# top.net
KiCad netlist of a schematic drawn in Altium Designer
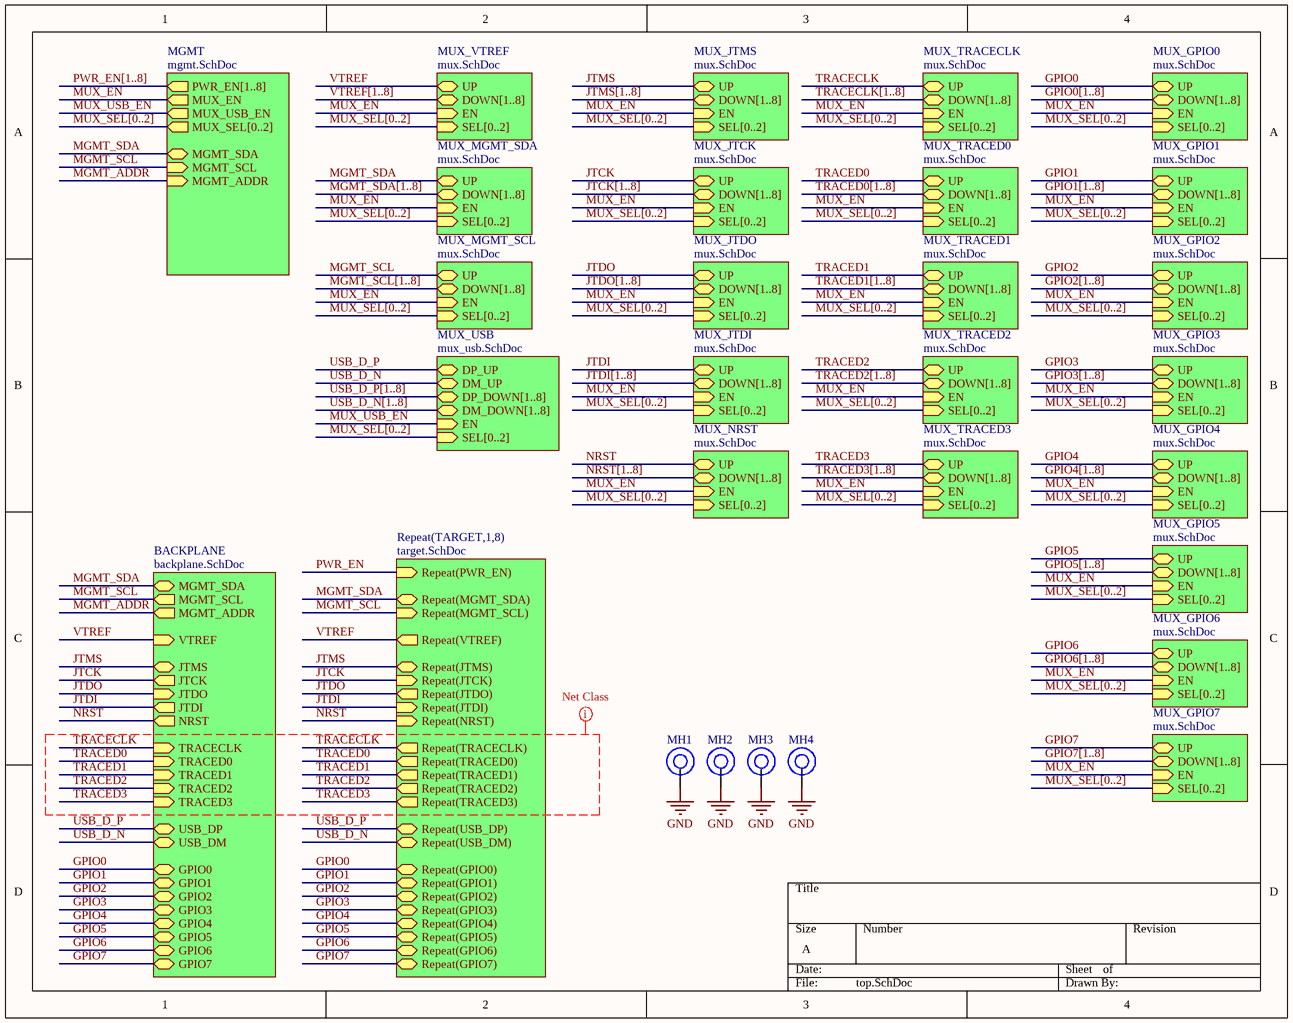
[diagram p0: top.SchDoc]

(export (version "E")
  (design (tool "Eeschema 10.0.6"))
  (components
    (comp (ref "MH1")
      (value "Mounting_Hole")
      (footprint "WA-SMSI_M2.5")
      (libsource (lib "misc") (part "Mounting_Hole"))
    )
    (comp (ref "MH2")
      (value "Mounting_Hole")
      (footprint "WA-SMSI_M2.5")
      (libsource (lib "misc") (part "Mounting_Hole"))
    )
    (comp (ref "MH3")
      (value "Mounting_Hole")
      (footprint "WA-SMSI_M2.5")
      (libsource (lib "misc") (part "Mounting_Hole"))
    )
    (comp (ref "MH4")
      (value "Mounting_Hole")
      (footprint "WA-SMSI_M2.5")
      (libsource (lib "misc") (part "Mounting_Hole"))
    )
  )
  (nets
    (net (code "248") (name "GND") (class "Default")
      (node (ref "MH1") (pin "1") (pintype "passive"))
      (node (ref "MH2") (pin "1") (pintype "passive"))
      (node (ref "MH3") (pin "1") (pintype "passive"))
      (node (ref "MH4") (pin "1") (pintype "passive"))
    )
  )
)
